# Platform.net
KiCad netlist of a schematic drawn in EAGLE
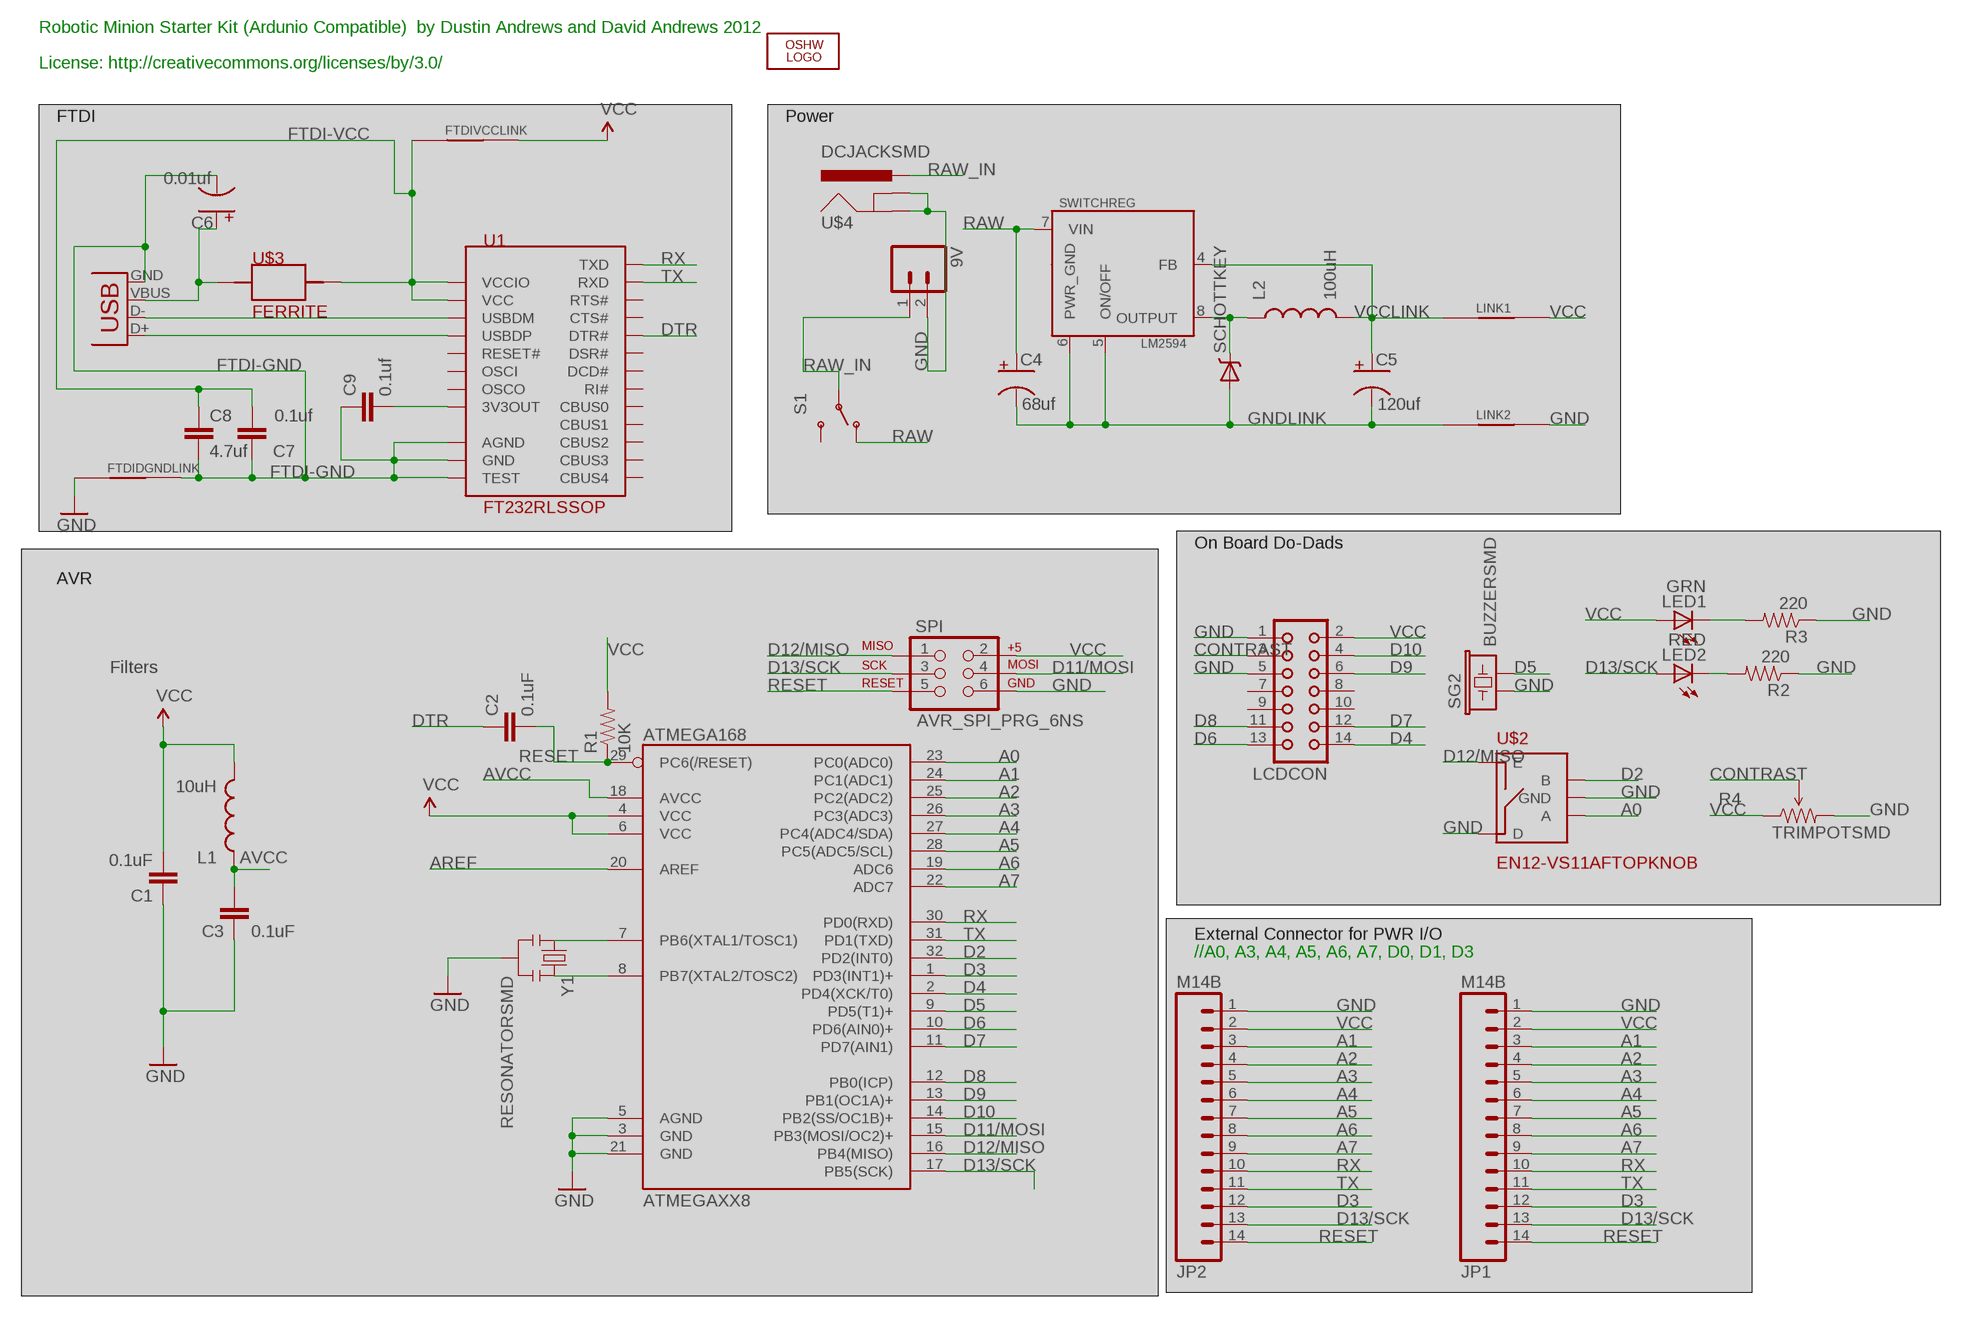
[diagram p0: schematic, sheet 1]

(export (version "E")
  (design (tool "Eeschema 10.0.6"))
  (components
    (comp (ref "9V")
      (value "M02PTH")
      (footprint "eagle-import:1X02")
      (libsource (lib "eagle-import") (part "M02PTH"))
    )
    (comp (ref "ATMEGAXX8")
      (value "ATMEGA168")
      (footprint "eagle-import:TQFP32-08")
      (libsource (lib "eagle-import") (part "ATMEGA168"))
    )
    (comp (ref "C1")
      (value "0.1uF")
      (footprint "eagle-import:0805")
      (libsource (lib "eagle-import") (part "CAP0805"))
    )
    (comp (ref "C2")
      (value "0.1uF")
      (footprint "eagle-import:0805")
      (libsource (lib "eagle-import") (part "CAP0805"))
    )
    (comp (ref "C3")
      (value "0.1uF")
      (footprint "eagle-import:0805")
      (libsource (lib "eagle-import") (part "CAP0805"))
    )
    (comp (ref "C4")
      (value "68uf")
      (footprint "eagle-import:F80")
      (libsource (lib "eagle-import") (part "CAP_POLF80"))
    )
    (comp (ref "C5")
      (value "120uf")
      (footprint "eagle-import:10X8CAP")
      (libsource (lib "eagle-import") (part "CAP_POL8X10"))
    )
    (comp (ref "C6")
      (value "0.01uf")
      (footprint "eagle-import:0805POL")
      (libsource (lib "eagle-import") (part "CAP_POL"))
    )
    (comp (ref "C7")
      (value "0.1uf")
      (footprint "eagle-import:0805")
      (libsource (lib "eagle-import") (part "CAP0805"))
    )
    (comp (ref "C8")
      (value "4.7uf")
      (footprint "eagle-import:0805")
      (libsource (lib "eagle-import") (part "CAP0805"))
    )
    (comp (ref "C9")
      (value "0.1uf")
      (footprint "eagle-import:0805")
      (libsource (lib "eagle-import") (part "CAP0805"))
    )
    (comp (ref "FTDIDGNDLINK")
      (value "LINK")
      (footprint "eagle-import:ISOLATOR")
      (libsource (lib "eagle-import") (part "LINK"))
    )
    (comp (ref "FTDIVCCLINK")
      (value "LINK")
      (footprint "eagle-import:ISOLATOR")
      (libsource (lib "eagle-import") (part "LINK"))
    )
    (comp (ref "JP1")
      (value "M14B")
      (footprint "eagle-import:1X14B")
      (libsource (lib "eagle-import") (part "M14B"))
    )
    (comp (ref "JP2")
      (value "M14B")
      (footprint "eagle-import:1X14B")
      (libsource (lib "eagle-import") (part "M14B"))
    )
    (comp (ref "L1")
      (value "10uH")
      (footprint "eagle-import:0805")
      (libsource (lib "eagle-import") (part "INDUCTOR0805"))
    )
    (comp (ref "L2")
      (value "100uH")
      (footprint "eagle-import:0805")
      (libsource (lib "eagle-import") (part "INDUCTOR0805"))
    )
    (comp (ref "LCDCON")
      (value "CON14")
      (footprint "eagle-import:CON14")
      (libsource (lib "eagle-import") (part "CON14"))
    )
    (comp (ref "LED1")
      (value "GRN")
      (footprint "eagle-import:LED-0805")
      (libsource (lib "eagle-import") (part "LED0805"))
    )
    (comp (ref "LED2")
      (value "RED")
      (footprint "eagle-import:LED-0805")
      (libsource (lib "eagle-import") (part "LED0805"))
    )
    (comp (ref "LINK1")
      (value "LINK")
      (footprint "eagle-import:ISOLATOR")
      (libsource (lib "eagle-import") (part "LINK"))
    )
    (comp (ref "LINK2")
      (value "LINK")
      (footprint "eagle-import:ISOLATOR")
      (libsource (lib "eagle-import") (part "LINK"))
    )
    (comp (ref "LOGO1")
      (value "OSHW_LOGO_10MILX0750-NT")
      (footprint "eagle-import:OSHW_10X750_NOTEXT")
      (libsource (lib "eagle-import") (part "OSHW_LOGO_10MILX0750-NT"))
    )
    (comp (ref "R1")
      (value "10K")
      (footprint "eagle-import:0805")
      (libsource (lib "eagle-import") (part "RESISTOR0805-RES"))
    )
    (comp (ref "R2")
      (value "220")
      (footprint "eagle-import:0805")
      (libsource (lib "eagle-import") (part "RESISTOR0805-RES"))
    )
    (comp (ref "R3")
      (value "220")
      (footprint "eagle-import:0805")
      (libsource (lib "eagle-import") (part "RESISTOR0805-RES"))
    )
    (comp (ref "R4")
      (value "TRIMPOTSMD")
      (footprint "eagle-import:TRIMPOT-3MM")
      (libsource (lib "eagle-import") (part "TRIMPOTSMD"))
    )
    (comp (ref "S1")
      (value "SWITCH-SPDT")
      (footprint "eagle-import:SWITCH-SPDT-SMT")
      (libsource (lib "eagle-import") (part "SWITCH-SPDT"))
    )
    (comp (ref "SCHOTTKEY")
      (value "DIODE-SCHOTTKY")
      (footprint "eagle-import:SOD-123")
      (libsource (lib "eagle-import") (part "DIODE-SCHOTTKY"))
    )
    (comp (ref "SG2")
      (value "BUZZERSMD")
      (footprint "eagle-import:BUZZER-CMT1603")
      (libsource (lib "eagle-import") (part "BUZZERSMD"))
    )
    (comp (ref "SPI")
      (value "AVR_SPI_PRG_6NS")
      (footprint "eagle-import:2X3-NS")
      (libsource (lib "eagle-import") (part "AVR_SPI_PRG_6NS"))
    )
    (comp (ref "SWITCHREG")
      (value "LM2594")
      (footprint "eagle-import:SOIC8")
      (libsource (lib "eagle-import") (part "LM2594"))
    )
    (comp (ref "U$2")
      (value "EN12-VS11AFTOPKNOB")
      (footprint "eagle-import:12MM_ROTATY_TOP")
      (libsource (lib "eagle-import") (part "EN12-VS11AFTOPKNOB"))
    )
    (comp (ref "U$3")
      (value "FERRITE")
      (footprint "eagle-import:0805")
      (libsource (lib "eagle-import") (part "FERRITE"))
    )
    (comp (ref "U$4")
      (value "DCJACKSMD")
      (footprint "eagle-import:JACK-SMD")
      (libsource (lib "eagle-import") (part "DCJACKSMD"))
    )
    (comp (ref "U1")
      (value "FT232RLSSOP")
      (footprint "eagle-import:SSOP28")
      (libsource (lib "eagle-import") (part "FT232RLSSOP"))
    )
    (comp (ref "X1")
      (value "USBSMD")
      (footprint "eagle-import:USB-MINIB")
      (libsource (lib "eagle-import") (part "USBSMD"))
    )
    (comp (ref "Y1")
      (value "RESONATORSMD")
      (footprint "eagle-import:RESONATOR-SMD")
      (libsource (lib "eagle-import") (part "RESONATORSMD"))
    )
  )
  (nets
    (net (code "1") (name "/A0") (class "Default")
      (node (ref "ATMEGAXX8") (pin "23") (pinfunction "PC0(ADC0)_23") (pintype "bidirectional"))
      (node (ref "U$2") (pin "A") (pinfunction "A_A") (pintype "bidirectional"))
    )
    (net (code "2") (name "/A1") (class "Default")
      (node (ref "ATMEGAXX8") (pin "24") (pinfunction "PC1(ADC1)_24") (pintype "bidirectional"))
      (node (ref "JP1") (pin "3") (pinfunction "3_3") (pintype "passive"))
      (node (ref "JP2") (pin "3") (pinfunction "3_3") (pintype "passive"))
    )
    (net (code "3") (name "/A2") (class "Default")
      (node (ref "ATMEGAXX8") (pin "25") (pinfunction "PC2(ADC2)_25") (pintype "bidirectional"))
      (node (ref "JP1") (pin "4") (pinfunction "4_4") (pintype "passive"))
      (node (ref "JP2") (pin "4") (pinfunction "4_4") (pintype "passive"))
    )
    (net (code "4") (name "/A3") (class "Default")
      (node (ref "ATMEGAXX8") (pin "26") (pinfunction "PC3(ADC3)_26") (pintype "bidirectional"))
      (node (ref "JP1") (pin "5") (pinfunction "5_5") (pintype "passive"))
      (node (ref "JP2") (pin "5") (pinfunction "5_5") (pintype "passive"))
    )
    (net (code "5") (name "/A4") (class "Default")
      (node (ref "ATMEGAXX8") (pin "27") (pinfunction "PC4(ADC4/SDA)_27") (pintype "bidirectional"))
      (node (ref "JP1") (pin "6") (pinfunction "6_6") (pintype "passive"))
      (node (ref "JP2") (pin "6") (pinfunction "6_6") (pintype "passive"))
    )
    (net (code "6") (name "/A5") (class "Default")
      (node (ref "ATMEGAXX8") (pin "28") (pinfunction "PC5(ADC5/SCL)_28") (pintype "bidirectional"))
      (node (ref "JP1") (pin "7") (pinfunction "7_7") (pintype "passive"))
      (node (ref "JP2") (pin "7") (pinfunction "7_7") (pintype "passive"))
    )
    (net (code "7") (name "/A6") (class "Default")
      (node (ref "ATMEGAXX8") (pin "19") (pinfunction "ADC6_19") (pintype "bidirectional"))
      (node (ref "JP1") (pin "8") (pinfunction "8_8") (pintype "passive"))
      (node (ref "JP2") (pin "8") (pinfunction "8_8") (pintype "passive"))
    )
    (net (code "8") (name "/A7") (class "Default")
      (node (ref "ATMEGAXX8") (pin "22") (pinfunction "ADC7_22") (pintype "bidirectional"))
      (node (ref "JP1") (pin "9") (pinfunction "9_9") (pintype "passive"))
      (node (ref "JP2") (pin "9") (pinfunction "9_9") (pintype "passive"))
    )
    (net (code "9") (name "/AREF") (class "Default")
      (node (ref "ATMEGAXX8") (pin "20") (pinfunction "AREF_20") (pintype "bidirectional"))
    )
    (net (code "10") (name "/AVCC") (class "Default")
      (node (ref "ATMEGAXX8") (pin "18") (pinfunction "AVCC_18") (pintype "bidirectional"))
      (node (ref "C3") (pin "2") (pinfunction "2_2") (pintype "passive"))
      (node (ref "L1") (pin "1") (pinfunction "1_1") (pintype "passive"))
    )
    (net (code "11") (name "/CONTRAST") (class "Default")
      (node (ref "LCDCON") (pin "3") (pinfunction "3_3") (pintype "passive"))
      (node (ref "R4") (pin "2") (pinfunction "WIPER_2") (pintype "passive"))
    )
    (net (code "12") (name "/D2") (class "Default")
      (node (ref "ATMEGAXX8") (pin "32") (pinfunction "PD2(INT0)_32") (pintype "bidirectional"))
      (node (ref "U$2") (pin "B") (pinfunction "B_B") (pintype "bidirectional"))
    )
    (net (code "13") (name "/D3") (class "Default")
      (node (ref "ATMEGAXX8") (pin "1") (pinfunction "PD3(INT1)+_1") (pintype "bidirectional"))
      (node (ref "JP1") (pin "12") (pinfunction "12_12") (pintype "passive"))
      (node (ref "JP2") (pin "12") (pinfunction "12_12") (pintype "passive"))
    )
    (net (code "14") (name "/D4") (class "Default")
      (node (ref "ATMEGAXX8") (pin "2") (pinfunction "PD4(XCK/T0)_2") (pintype "bidirectional"))
      (node (ref "LCDCON") (pin "14") (pinfunction "14_14") (pintype "passive"))
    )
    (net (code "15") (name "/D5") (class "Default")
      (node (ref "ATMEGAXX8") (pin "9") (pinfunction "PD5(T1)+_9") (pintype "bidirectional"))
      (node (ref "SG2") (pin "P$2") (pinfunction "2_P$2") (pintype "passive"))
    )
    (net (code "16") (name "/D6") (class "Default")
      (node (ref "ATMEGAXX8") (pin "10") (pinfunction "PD6(AIN0)+_10") (pintype "bidirectional"))
      (node (ref "LCDCON") (pin "13") (pinfunction "13_13") (pintype "passive"))
    )
    (net (code "17") (name "/D7") (class "Default")
      (node (ref "ATMEGAXX8") (pin "11") (pinfunction "PD7(AIN1)_11") (pintype "bidirectional"))
      (node (ref "LCDCON") (pin "12") (pinfunction "12_12") (pintype "passive"))
    )
    (net (code "18") (name "/D8") (class "Default")
      (node (ref "ATMEGAXX8") (pin "12") (pinfunction "PB0(ICP)_12") (pintype "bidirectional"))
      (node (ref "LCDCON") (pin "11") (pinfunction "11_11") (pintype "passive"))
    )
    (net (code "19") (name "/D9") (class "Default")
      (node (ref "ATMEGAXX8") (pin "13") (pinfunction "PB1(OC1A)+_13") (pintype "bidirectional"))
      (node (ref "LCDCON") (pin "6") (pinfunction "6_6") (pintype "passive"))
    )
    (net (code "20") (name "/D10") (class "Default")
      (node (ref "ATMEGAXX8") (pin "14") (pinfunction "PB2(SS/OC1B)+_14") (pintype "bidirectional"))
      (node (ref "LCDCON") (pin "4") (pinfunction "4_4") (pintype "passive"))
    )
    (net (code "21") (name "/D11{slash}MOSI") (class "Default")
      (node (ref "ATMEGAXX8") (pin "15") (pinfunction "PB3(MOSI/OC2)+_15") (pintype "bidirectional"))
      (node (ref "SPI") (pin "4") (pinfunction "4_4") (pintype "passive"))
    )
    (net (code "22") (name "/D12{slash}MISO") (class "Default")
      (node (ref "ATMEGAXX8") (pin "16") (pinfunction "PB4(MISO)_16") (pintype "bidirectional"))
      (node (ref "SPI") (pin "1") (pinfunction "1_1") (pintype "passive"))
      (node (ref "U$2") (pin "E") (pinfunction "E_E") (pintype "bidirectional"))
    )
    (net (code "23") (name "/D13{slash}SCK") (class "Default")
      (node (ref "ATMEGAXX8") (pin "17") (pinfunction "PB5(SCK)_17") (pintype "bidirectional"))
      (node (ref "JP1") (pin "13") (pinfunction "13_13") (pintype "passive"))
      (node (ref "JP2") (pin "13") (pinfunction "13_13") (pintype "passive"))
      (node (ref "LED2") (pin "A") (pinfunction "A_A") (pintype "passive"))
      (node (ref "SPI") (pin "3") (pinfunction "3_3") (pintype "passive"))
    )
    (net (code "24") (name "/DTR") (class "Default")
      (node (ref "C2") (pin "1") (pinfunction "1_1") (pintype "passive"))
      (node (ref "U1") (pin "2") (pinfunction "DTR#_2") (pintype "bidirectional"))
    )
    (net (code "25") (name "/FTDI-GND") (class "Default")
      (node (ref "C6") (pin "-") (pinfunction "-_-") (pintype "bidirectional"))
      (node (ref "C7") (pin "1") (pinfunction "1_1") (pintype "passive"))
      (node (ref "C8") (pin "2") (pinfunction "2_2") (pintype "passive"))
      (node (ref "C9") (pin "1") (pinfunction "1_1") (pintype "passive"))
      (node (ref "FTDIDGNDLINK") (pin "P$2") (pinfunction "P$2_P$2") (pintype "bidirectional"))
      (node (ref "U1") (pin "18") (pinfunction "GND_18") (pintype "bidirectional"))
      (node (ref "U1") (pin "21") (pinfunction "GND_21") (pintype "bidirectional"))
      (node (ref "U1") (pin "25") (pinfunction "AGND_25") (pintype "bidirectional"))
      (node (ref "U1") (pin "26") (pinfunction "TEST_26") (pintype "bidirectional"))
      (node (ref "U1") (pin "7") (pinfunction "GND_7") (pintype "bidirectional"))
      (node (ref "X1") (pin "GND") (pinfunction "GND_GND") (pintype "bidirectional"))
    )
    (net (code "26") (name "/FTDI-VCC") (class "Default")
      (node (ref "C7") (pin "2") (pinfunction "2_2") (pintype "passive"))
      (node (ref "C8") (pin "1") (pinfunction "1_1") (pintype "passive"))
      (node (ref "FTDIVCCLINK") (pin "P$1") (pinfunction "P$1_P$1") (pintype "bidirectional"))
      (node (ref "U$3") (pin "2") (pinfunction "P$2_2") (pintype "bidirectional"))
      (node (ref "U1") (pin "20") (pinfunction "VCC_20") (pintype "bidirectional"))
      (node (ref "U1") (pin "4") (pinfunction "VCCIO_4") (pintype "bidirectional"))
    )
    (net (code "27") (name "/GNDLINK") (class "Default")
      (node (ref "C4") (pin "-") (pinfunction "-_-") (pintype "bidirectional"))
      (node (ref "C5") (pin "-") (pinfunction "-_-") (pintype "bidirectional"))
      (node (ref "LINK2") (pin "P$1") (pinfunction "P$1_P$1") (pintype "bidirectional"))
      (node (ref "SCHOTTKEY") (pin "ANODE") (pinfunction "A_ANODE") (pintype "passive"))
      (node (ref "SWITCHREG") (pin "5") (pinfunction "ON/OFF_5") (pintype "bidirectional"))
      (node (ref "SWITCHREG") (pin "6") (pinfunction "PWR_GND_6") (pintype "bidirectional"))
    )
    (net (code "28") (name "/RAW") (class "Default")
      (node (ref "C4") (pin "+") (pinfunction "+_+") (pintype "bidirectional"))
      (node (ref "S1") (pin "1") (pinfunction "O_1") (pintype "passive"))
      (node (ref "SWITCHREG") (pin "7") (pinfunction "VIN_7") (pintype "bidirectional"))
    )
    (net (code "29") (name "/RAW_IN") (class "Default")
      (node (ref "9V") (pin "1") (pinfunction "1_1") (pintype "passive"))
      (node (ref "S1") (pin "2") (pinfunction "P_2") (pintype "passive"))
      (node (ref "U$4") (pin "2") (pinfunction "PWR_2") (pintype "bidirectional"))
      (node (ref "U$4") (pin "3") (pinfunction "PWR_3") (pintype "bidirectional"))
    )
    (net (code "30") (name "/RESET") (class "Default")
      (node (ref "ATMEGAXX8") (pin "29") (pinfunction "PC6(/RESET)_29") (pintype "bidirectional"))
      (node (ref "C2") (pin "2") (pinfunction "2_2") (pintype "passive"))
      (node (ref "JP1") (pin "14") (pinfunction "14_14") (pintype "passive"))
      (node (ref "JP2") (pin "14") (pinfunction "14_14") (pintype "passive"))
      (node (ref "R1") (pin "1") (pinfunction "1_1") (pintype "passive"))
      (node (ref "SPI") (pin "5") (pinfunction "5_5") (pintype "passive"))
    )
    (net (code "31") (name "/RX") (class "Default")
      (node (ref "ATMEGAXX8") (pin "30") (pinfunction "PD0(RXD)_30") (pintype "bidirectional"))
      (node (ref "JP1") (pin "10") (pinfunction "10_10") (pintype "passive"))
      (node (ref "JP2") (pin "10") (pinfunction "10_10") (pintype "passive"))
      (node (ref "U1") (pin "1") (pinfunction "TXD_1") (pintype "bidirectional"))
    )
    (net (code "32") (name "/TX") (class "Default")
      (node (ref "ATMEGAXX8") (pin "31") (pinfunction "PD1(TXD)_31") (pintype "bidirectional"))
      (node (ref "JP1") (pin "11") (pinfunction "11_11") (pintype "passive"))
      (node (ref "JP2") (pin "11") (pinfunction "11_11") (pintype "passive"))
      (node (ref "U1") (pin "5") (pinfunction "RXD_5") (pintype "bidirectional"))
    )
    (net (code "33") (name "/VCCLINK") (class "Default")
      (node (ref "C5") (pin "+") (pinfunction "+_+") (pintype "bidirectional"))
      (node (ref "L2") (pin "2") (pinfunction "2_2") (pintype "passive"))
      (node (ref "LINK1") (pin "P$1") (pinfunction "P$1_P$1") (pintype "bidirectional"))
      (node (ref "SWITCHREG") (pin "4") (pinfunction "FB_4") (pintype "bidirectional"))
    )
    (net (code "34") (name "GND") (class "Default")
      (node (ref "9V") (pin "2") (pinfunction "2_2") (pintype "passive"))
      (node (ref "ATMEGAXX8") (pin "21") (pinfunction "GND_21") (pintype "bidirectional"))
      (node (ref "ATMEGAXX8") (pin "3") (pinfunction "GND_3") (pintype "bidirectional"))
      (node (ref "ATMEGAXX8") (pin "5") (pinfunction "AGND_5") (pintype "bidirectional"))
      (node (ref "C1") (pin "1") (pinfunction "1_1") (pintype "passive"))
      (node (ref "C3") (pin "1") (pinfunction "1_1") (pintype "passive"))
      (node (ref "FTDIDGNDLINK") (pin "P$1") (pinfunction "P$1_P$1") (pintype "bidirectional"))
      (node (ref "JP1") (pin "1") (pinfunction "1_1") (pintype "passive"))
      (node (ref "JP2") (pin "1") (pinfunction "1_1") (pintype "passive"))
      (node (ref "LCDCON") (pin "1") (pinfunction "1_1") (pintype "passive"))
      (node (ref "LCDCON") (pin "5") (pinfunction "5_5") (pintype "passive"))
      (node (ref "LINK2") (pin "P$2") (pinfunction "P$2_P$2") (pintype "bidirectional"))
      (node (ref "R2") (pin "1") (pinfunction "1_1") (pintype "passive"))
      (node (ref "R3") (pin "1") (pinfunction "1_1") (pintype "passive"))
      (node (ref "R4") (pin "3") (pinfunction "CW_3") (pintype "passive"))
      (node (ref "SG2") (pin "P$1") (pinfunction "1_P$1") (pintype "passive"))
      (node (ref "SPI") (pin "6") (pinfunction "6_6") (pintype "passive"))
      (node (ref "U$2") (pin "C") (pinfunction "GND_C") (pintype "bidirectional"))
      (node (ref "U$2") (pin "D") (pinfunction "D_D") (pintype "bidirectional"))
      (node (ref "U$4") (pin "1A") (pinfunction "GND_1A") (pintype "bidirectional"))
      (node (ref "U$4") (pin "1B") (pinfunction "GNDBREAK_1B") (pintype "bidirectional"))
      (node (ref "Y1") (pin "2") (pinfunction "2_2") (pintype "passive"))
    )
    (net (code "35") (name "Net-(ATMEGAXX8-PB6(XTAL1{slash}TOSC1))") (class "Default")
      (node (ref "ATMEGAXX8") (pin "7") (pinfunction "PB6(XTAL1/TOSC1)_7") (pintype "bidirectional"))
      (node (ref "Y1") (pin "1") (pinfunction "1_1") (pintype "passive"))
    )
    (net (code "36") (name "Net-(ATMEGAXX8-PB7(XTAL2{slash}TOSC2))") (class "Default")
      (node (ref "ATMEGAXX8") (pin "8") (pinfunction "PB7(XTAL2/TOSC2)_8") (pintype "bidirectional"))
      (node (ref "Y1") (pin "3") (pinfunction "3_3") (pintype "passive"))
    )
    (net (code "37") (name "Net-(LED1-PadC)") (class "Default")
      (node (ref "LED1") (pin "C") (pinfunction "C_C") (pintype "passive"))
      (node (ref "R3") (pin "2") (pinfunction "2_2") (pintype "passive"))
    )
    (net (code "38") (name "Net-(LED2-PadC)") (class "Default")
      (node (ref "LED2") (pin "C") (pinfunction "C_C") (pintype "passive"))
      (node (ref "R2") (pin "2") (pinfunction "2_2") (pintype "passive"))
    )
    (net (code "39") (name "Net-(SCHOTTKEY-C)") (class "Default")
      (node (ref "L2") (pin "1") (pinfunction "1_1") (pintype "passive"))
      (node (ref "SCHOTTKEY") (pin "CATHODE") (pinfunction "C_CATHODE") (pintype "passive"))
      (node (ref "SWITCHREG") (pin "8") (pinfunction "OUTPUT_8") (pintype "bidirectional"))
    )
    (net (code "40") (name "Net-(U$3-P$1)") (class "Default")
      (node (ref "C6") (pin "+") (pinfunction "+_+") (pintype "bidirectional"))
      (node (ref "U$3") (pin "1") (pinfunction "P$1_1") (pintype "bidirectional"))
      (node (ref "X1") (pin "VBUS") (pinfunction "VBUS_VBUS") (pintype "bidirectional"))
    )
    (net (code "41") (name "Net-(U1-3V3OUT)") (class "Default")
      (node (ref "C9") (pin "2") (pinfunction "2_2") (pintype "passive"))
      (node (ref "U1") (pin "17") (pinfunction "3V3OUT_17") (pintype "bidirectional"))
    )
    (net (code "42") (name "Net-(U1-USBDM)") (class "Default")
      (node (ref "U1") (pin "16") (pinfunction "USBDM_16") (pintype "bidirectional"))
      (node (ref "X1") (pin "D-") (pinfunction "D-_D-") (pintype "bidirectional"))
    )
    (net (code "43") (name "Net-(U1-USBDP)") (class "Default")
      (node (ref "U1") (pin "15") (pinfunction "USBDP_15") (pintype "bidirectional"))
      (node (ref "X1") (pin "D+") (pinfunction "D+_D+") (pintype "bidirectional"))
    )
    (net (code "44") (name "VCC") (class "Default")
      (node (ref "ATMEGAXX8") (pin "4") (pinfunction "VCC_4") (pintype "bidirectional"))
      (node (ref "ATMEGAXX8") (pin "6") (pinfunction "VCC_6") (pintype "bidirectional"))
      (node (ref "C1") (pin "2") (pinfunction "2_2") (pintype "passive"))
      (node (ref "FTDIVCCLINK") (pin "P$2") (pinfunction "P$2_P$2") (pintype "bidirectional"))
      (node (ref "JP1") (pin "2") (pinfunction "2_2") (pintype "passive"))
      (node (ref "JP2") (pin "2") (pinfunction "2_2") (pintype "passive"))
      (node (ref "L1") (pin "2") (pinfunction "2_2") (pintype "passive"))
      (node (ref "LCDCON") (pin "2") (pinfunction "2_2") (pintype "passive"))
      (node (ref "LED1") (pin "A") (pinfunction "A_A") (pintype "passive"))
      (node (ref "LINK1") (pin "P$2") (pinfunction "P$2_P$2") (pintype "bidirectional"))
      (node (ref "R1") (pin "2") (pinfunction "2_2") (pintype "passive"))
      (node (ref "R4") (pin "1") (pinfunction "CCW_1") (pintype "passive"))
      (node (ref "SPI") (pin "2") (pinfunction "2_2") (pintype "passive"))
    )
    (net (code "45") (name "unconnected-(LCDCON-Pad7)") (class "Default")
      (node (ref "LCDCON") (pin "7") (pinfunction "7_7") (pintype "passive"))
    )
    (net (code "46") (name "unconnected-(LCDCON-Pad8)") (class "Default")
      (node (ref "LCDCON") (pin "8") (pinfunction "8_8") (pintype "passive"))
    )
    (net (code "47") (name "unconnected-(LCDCON-Pad9)") (class "Default")
      (node (ref "LCDCON") (pin "9") (pinfunction "9_9") (pintype "passive"))
    )
    (net (code "48") (name "unconnected-(LCDCON-Pad10)") (class "Default")
      (node (ref "LCDCON") (pin "10") (pinfunction "10_10") (pintype "passive"))
    )
    (net (code "49") (name "unconnected-(S1-S-Pad3)") (class "Default")
      (node (ref "S1") (pin "3") (pinfunction "S_3") (pintype "passive"))
    )
    (net (code "50") (name "unconnected-(U1-CBUS0-Pad23)") (class "Default")
      (node (ref "U1") (pin "23") (pinfunction "CBUS0_23") (pintype "bidirectional"))
    )
    (net (code "51") (name "unconnected-(U1-CBUS1-Pad22)") (class "Default")
      (node (ref "U1") (pin "22") (pinfunction "CBUS1_22") (pintype "bidirectional"))
    )
    (net (code "52") (name "unconnected-(U1-CBUS2-Pad13)") (class "Default")
      (node (ref "U1") (pin "13") (pinfunction "CBUS2_13") (pintype "bidirectional"))
    )
    (net (code "53") (name "unconnected-(U1-CBUS3-Pad14)") (class "Default")
      (node (ref "U1") (pin "14") (pinfunction "CBUS3_14") (pintype "bidirectional"))
    )
    (net (code "54") (name "unconnected-(U1-CBUS4-Pad12)") (class "Default")
      (node (ref "U1") (pin "12") (pinfunction "CBUS4_12") (pintype "bidirectional"))
    )
    (net (code "55") (name "unconnected-(U1-CTS#-Pad11)") (class "Default")
      (node (ref "U1") (pin "11") (pinfunction "CTS#_11") (pintype "bidirectional"))
    )
    (net (code "56") (name "unconnected-(U1-DCD#-Pad10)") (class "Default")
      (node (ref "U1") (pin "10") (pinfunction "DCD#_10") (pintype "bidirectional"))
    )
    (net (code "57") (name "unconnected-(U1-DSR#-Pad9)") (class "Default")
      (node (ref "U1") (pin "9") (pinfunction "DSR#_9") (pintype "bidirectional"))
    )
    (net (code "58") (name "unconnected-(U1-OSCI-Pad27)") (class "Default")
      (node (ref "U1") (pin "27") (pinfunction "OSCI_27") (pintype "bidirectional"))
    )
    (net (code "59") (name "unconnected-(U1-OSCO-Pad28)") (class "Default")
      (node (ref "U1") (pin "28") (pinfunction "OSCO_28") (pintype "bidirectional"))
    )
    (net (code "60") (name "unconnected-(U1-RESET#-Pad19)") (class "Default")
      (node (ref "U1") (pin "19") (pinfunction "RESET#_19") (pintype "bidirectional"))
    )
    (net (code "61") (name "unconnected-(U1-RI#-Pad6)") (class "Default")
      (node (ref "U1") (pin "6") (pinfunction "RI#_6") (pintype "bidirectional"))
    )
    (net (code "62") (name "unconnected-(U1-RTS#-Pad3)") (class "Default")
      (node (ref "U1") (pin "3") (pinfunction "RTS#_3") (pintype "bidirectional"))
    )
  )
)
